# isg-clock-generator-rev1.net
KiCad netlist of a schematic drawn in EAGLE
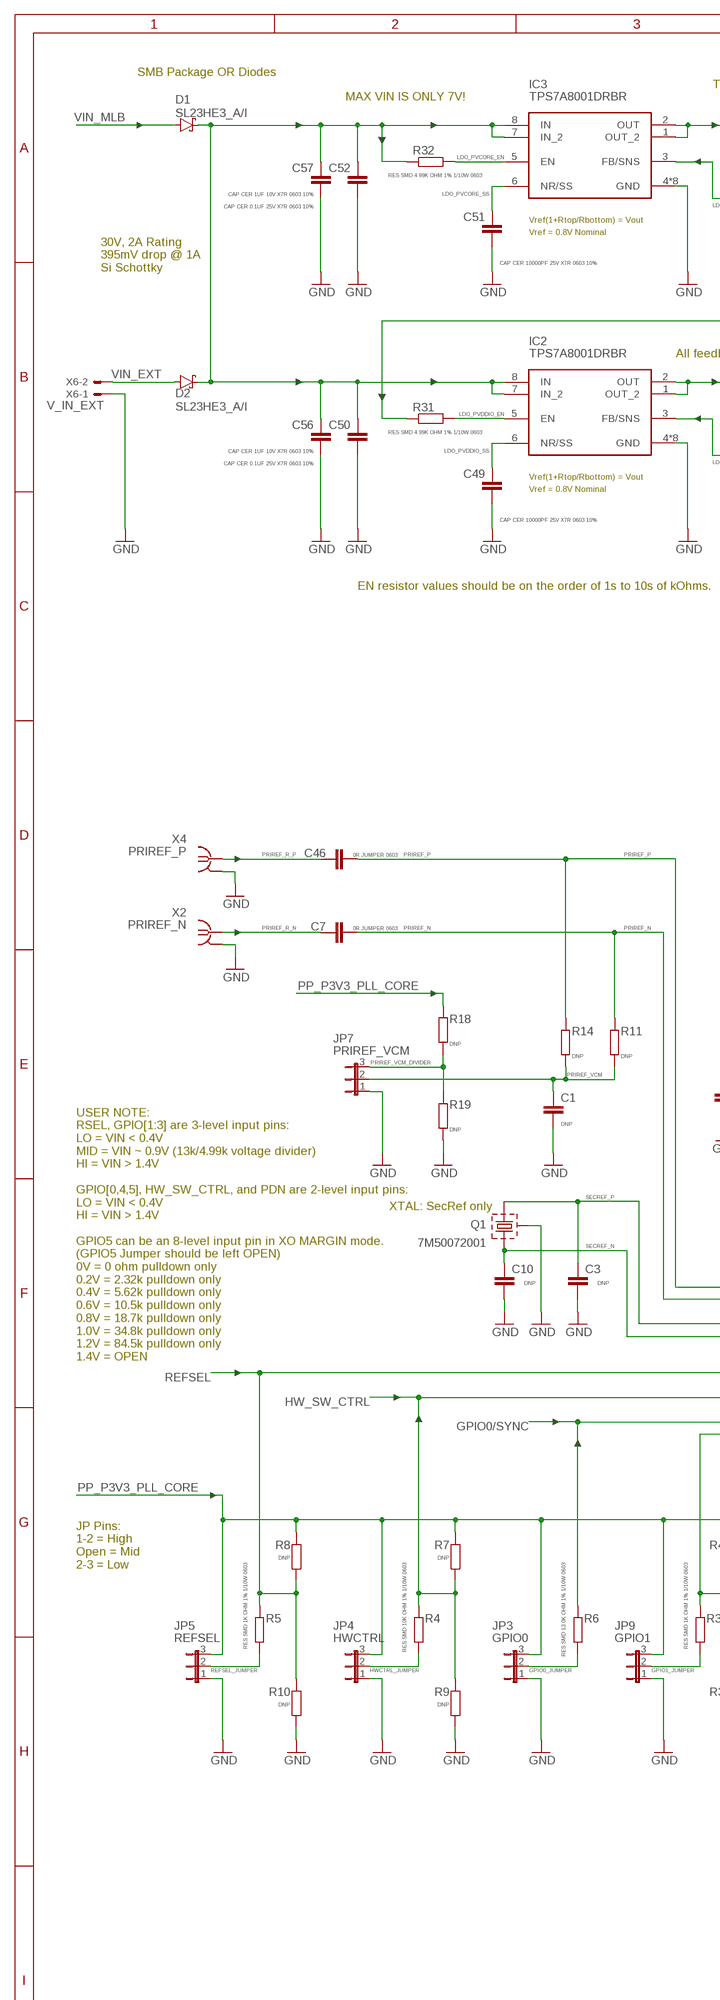
[diagram p0: schematic, sheet 1, part 1 of 2]
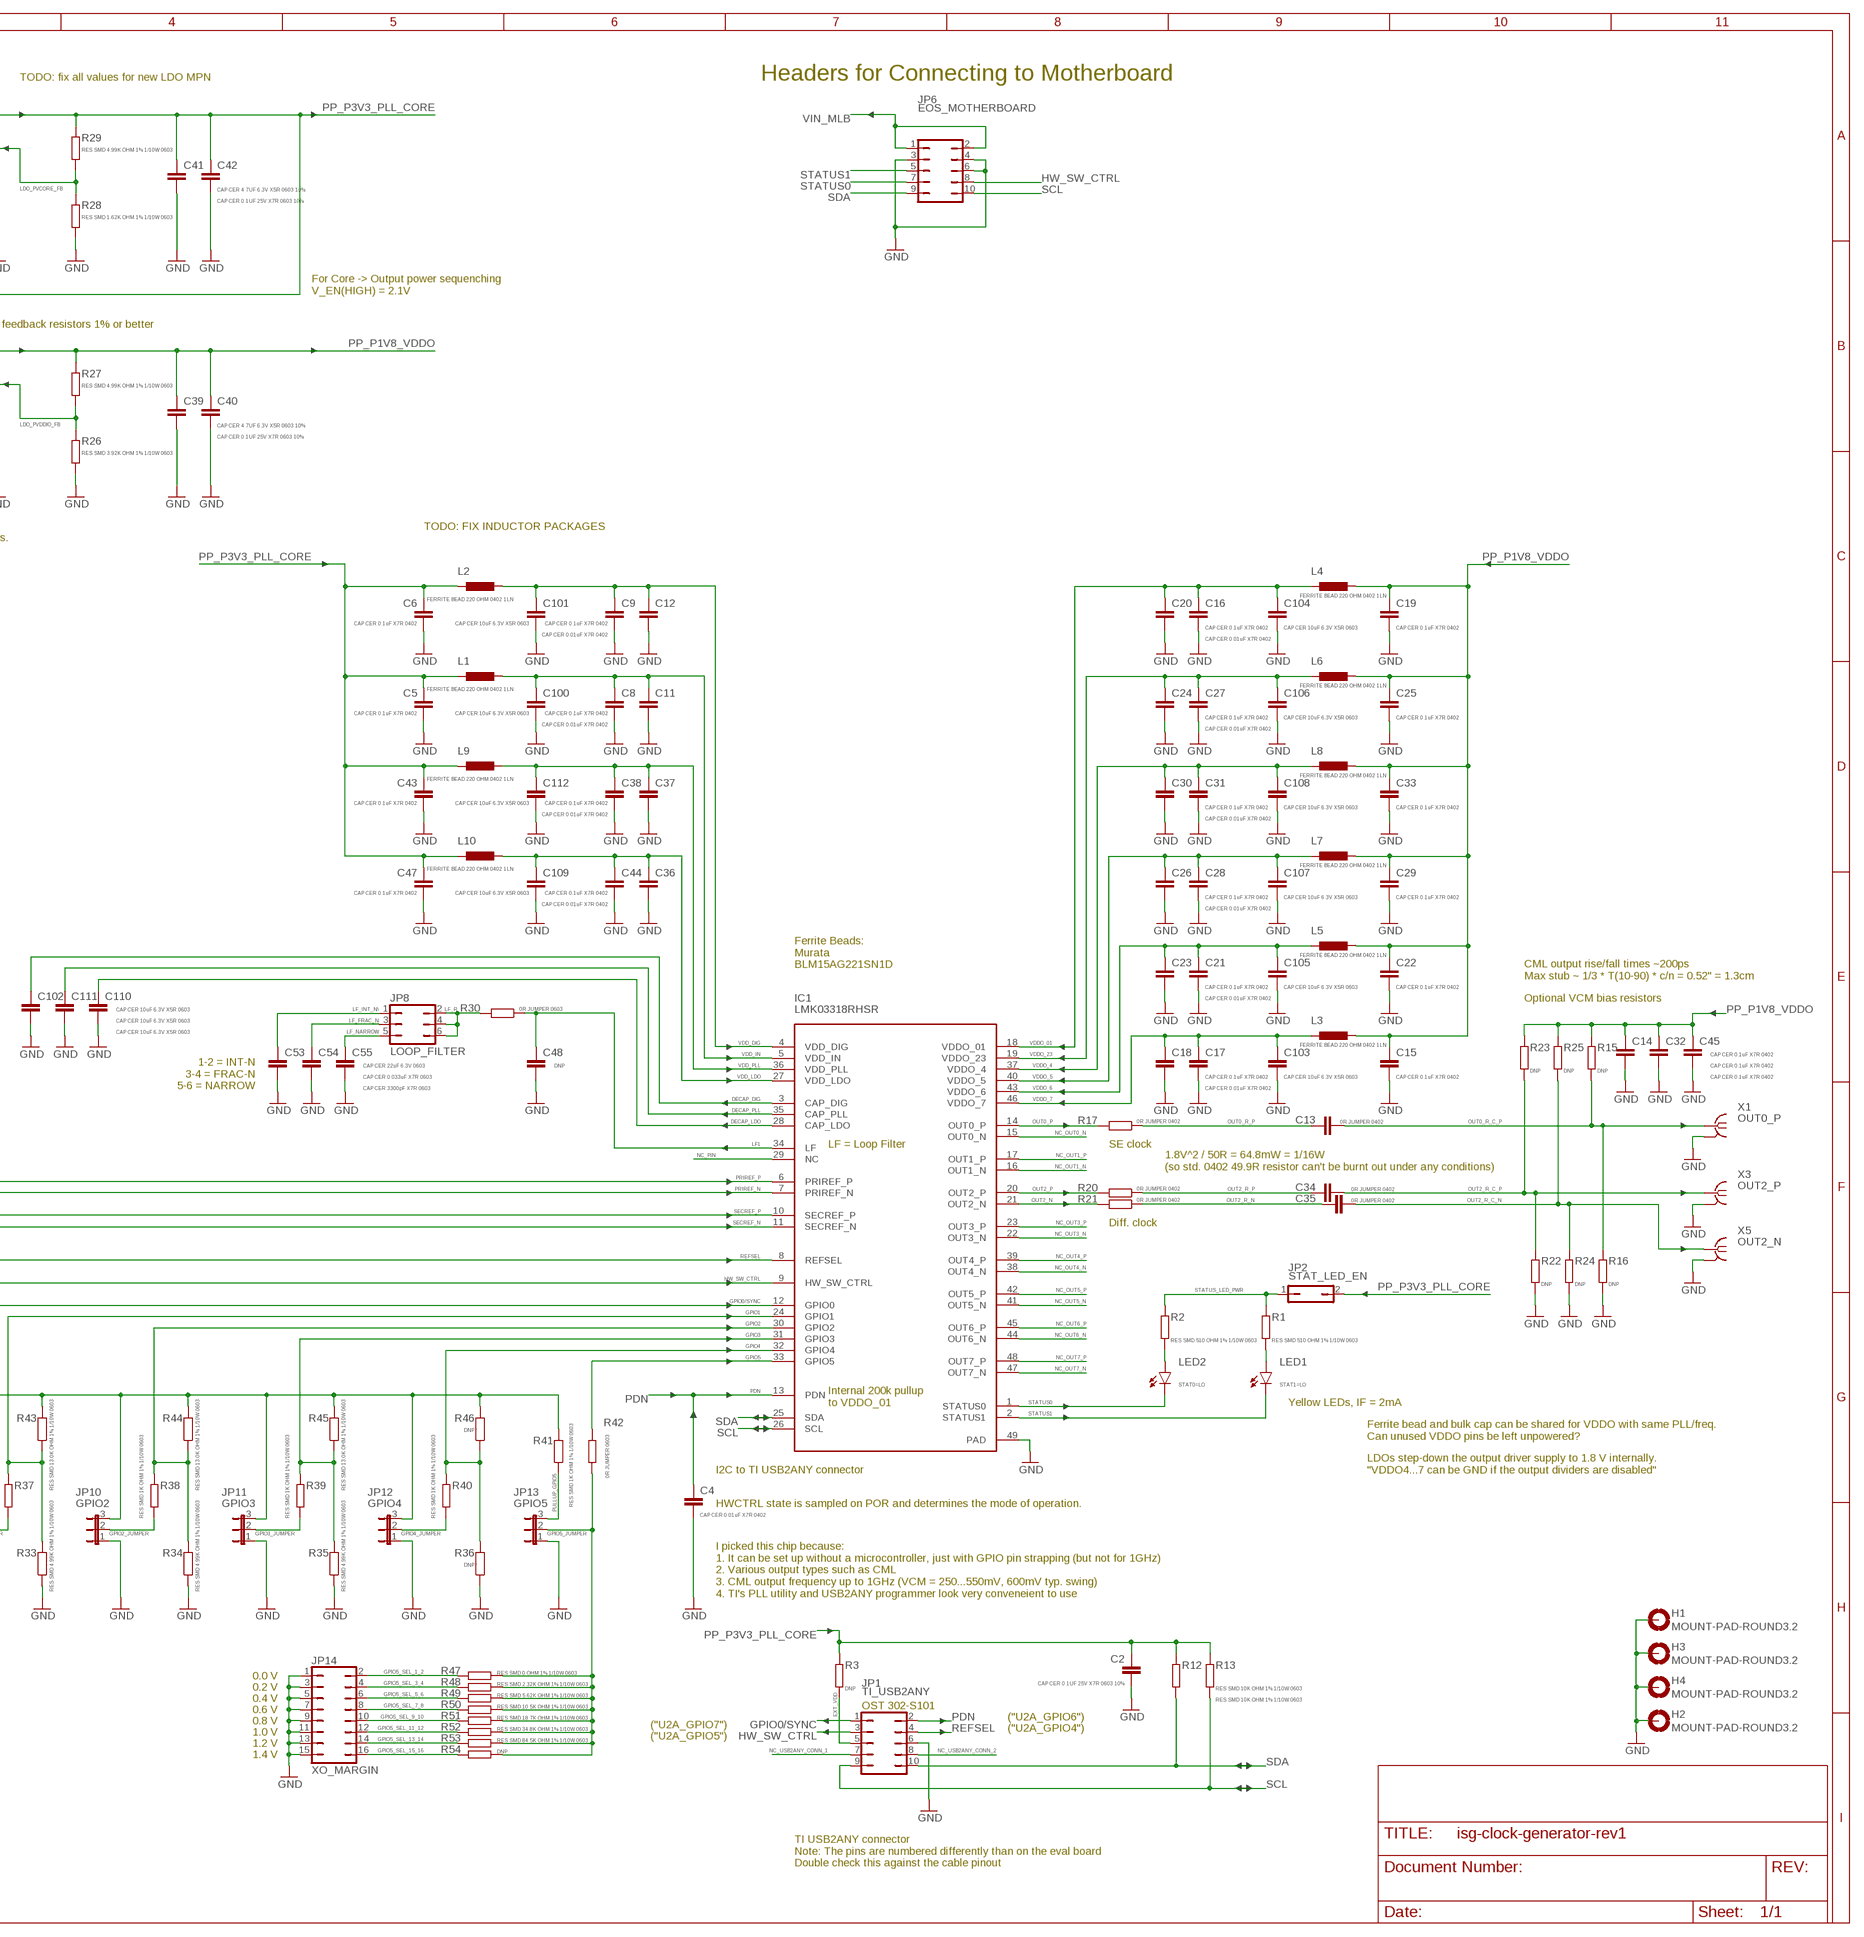
[diagram p1: schematic, sheet 1, part 2 of 2]

(export (version "E")
  (design (tool "Eeschema 10.0.6"))
  (components
    (comp (ref "C1")
      (value "DNP")
      (footprint "eagle-import:C0603")
      (libsource (lib "eagle-import") (part "C-EUC0603"))
    )
    (comp (ref "C2")
      (value "CAP CER 0.1UF 25V X7R 0603 10%")
      (footprint "eagle-import:C0603")
      (libsource (lib "eagle-import") (part "C-EUC0603"))
    )
    (comp (ref "C3")
      (value "DNP")
      (footprint "eagle-import:C0603")
      (libsource (lib "eagle-import") (part "C-EUC0603"))
    )
    (comp (ref "C4")
      (value "CAP CER 0.01uF X7R 0402")
      (footprint "eagle-import:C0402")
      (libsource (lib "eagle-import") (part "C-EUC0402"))
    )
    (comp (ref "C5")
      (value "CAP CER 0.1uF X7R 0402")
      (footprint "eagle-import:C0402")
      (libsource (lib "eagle-import") (part "C-EUC0402"))
    )
    (comp (ref "C6")
      (value "CAP CER 0.1uF X7R 0402")
      (footprint "eagle-import:C0402")
      (libsource (lib "eagle-import") (part "C-EUC0402"))
    )
    (comp (ref "C7")
      (value "0R JUMPER 0603")
      (footprint "eagle-import:C0603")
      (libsource (lib "eagle-import") (part "C-EUC0603"))
    )
    (comp (ref "C8")
      (value "CAP CER 0.1uF X7R 0402")
      (footprint "eagle-import:C0402")
      (libsource (lib "eagle-import") (part "C-EUC0402"))
    )
    (comp (ref "C9")
      (value "CAP CER 0.1uF X7R 0402")
      (footprint "eagle-import:C0402")
      (libsource (lib "eagle-import") (part "C-EUC0402"))
    )
    (comp (ref "C10")
      (value "DNP")
      (footprint "eagle-import:C0603")
      (libsource (lib "eagle-import") (part "C-EUC0603"))
    )
    (comp (ref "C11")
      (value "CAP CER 0.01uF X7R 0402")
      (footprint "eagle-import:C0402")
      (libsource (lib "eagle-import") (part "C-EUC0402"))
    )
    (comp (ref "C12")
      (value "CAP CER 0.01uF X7R 0402")
      (footprint "eagle-import:C0402")
      (libsource (lib "eagle-import") (part "C-EUC0402"))
    )
    (comp (ref "C13")
      (value "0R JUMPER 0402")
      (footprint "eagle-import:C0402")
      (libsource (lib "eagle-import") (part "C-EUC0402"))
    )
    (comp (ref "C14")
      (value "CAP CER 0.1uF X7R 0402")
      (footprint "eagle-import:C0402")
      (libsource (lib "eagle-import") (part "C-EUC0402"))
    )
    (comp (ref "C15")
      (value "CAP CER 0.1uF X7R 0402")
      (footprint "eagle-import:C0402")
      (libsource (lib "eagle-import") (part "C-EUC0402"))
    )
    (comp (ref "C16")
      (value "CAP CER 0.1uF X7R 0402")
      (footprint "eagle-import:C0402")
      (libsource (lib "eagle-import") (part "C-EUC0402"))
    )
    (comp (ref "C17")
      (value "CAP CER 0.1uF X7R 0402")
      (footprint "eagle-import:C0402")
      (libsource (lib "eagle-import") (part "C-EUC0402"))
    )
    (comp (ref "C18")
      (value "CAP CER 0.01uF X7R 0402")
      (footprint "eagle-import:C0402")
      (libsource (lib "eagle-import") (part "C-EUC0402"))
    )
    (comp (ref "C19")
      (value "CAP CER 0.1uF X7R 0402")
      (footprint "eagle-import:C0402")
      (libsource (lib "eagle-import") (part "C-EUC0402"))
    )
    (comp (ref "C20")
      (value "CAP CER 0.01uF X7R 0402")
      (footprint "eagle-import:C0402")
      (libsource (lib "eagle-import") (part "C-EUC0402"))
    )
    (comp (ref "C21")
      (value "CAP CER 0.1uF X7R 0402")
      (footprint "eagle-import:C0402")
      (libsource (lib "eagle-import") (part "C-EUC0402"))
    )
    (comp (ref "C22")
      (value "CAP CER 0.1uF X7R 0402")
      (footprint "eagle-import:C0402")
      (libsource (lib "eagle-import") (part "C-EUC0402"))
    )
    (comp (ref "C23")
      (value "CAP CER 0.01uF X7R 0402")
      (footprint "eagle-import:C0402")
      (libsource (lib "eagle-import") (part "C-EUC0402"))
    )
    (comp (ref "C24")
      (value "CAP CER 0.01uF X7R 0402")
      (footprint "eagle-import:C0402")
      (libsource (lib "eagle-import") (part "C-EUC0402"))
    )
    (comp (ref "C25")
      (value "CAP CER 0.1uF X7R 0402")
      (footprint "eagle-import:C0402")
      (libsource (lib "eagle-import") (part "C-EUC0402"))
    )
    (comp (ref "C26")
      (value "CAP CER 0.01uF X7R 0402")
      (footprint "eagle-import:C0402")
      (libsource (lib "eagle-import") (part "C-EUC0402"))
    )
    (comp (ref "C27")
      (value "CAP CER 0.1uF X7R 0402")
      (footprint "eagle-import:C0402")
      (libsource (lib "eagle-import") (part "C-EUC0402"))
    )
    (comp (ref "C28")
      (value "CAP CER 0.1uF X7R 0402")
      (footprint "eagle-import:C0402")
      (libsource (lib "eagle-import") (part "C-EUC0402"))
    )
    (comp (ref "C29")
      (value "CAP CER 0.1uF X7R 0402")
      (footprint "eagle-import:C0402")
      (libsource (lib "eagle-import") (part "C-EUC0402"))
    )
    (comp (ref "C30")
      (value "CAP CER 0.01uF X7R 0402")
      (footprint "eagle-import:C0402")
      (libsource (lib "eagle-import") (part "C-EUC0402"))
    )
    (comp (ref "C31")
      (value "CAP CER 0.1uF X7R 0402")
      (footprint "eagle-import:C0402")
      (libsource (lib "eagle-import") (part "C-EUC0402"))
    )
    (comp (ref "C32")
      (value "CAP CER 0.1uF X7R 0402")
      (footprint "eagle-import:C0402")
      (libsource (lib "eagle-import") (part "C-EUC0402"))
    )
    (comp (ref "C33")
      (value "CAP CER 0.1uF X7R 0402")
      (footprint "eagle-import:C0402")
      (libsource (lib "eagle-import") (part "C-EUC0402"))
    )
    (comp (ref "C34")
      (value "0R JUMPER 0402")
      (footprint "eagle-import:C0402")
      (libsource (lib "eagle-import") (part "C-EUC0402"))
    )
    (comp (ref "C35")
      (value "0R JUMPER 0402")
      (footprint "eagle-import:C0402")
      (libsource (lib "eagle-import") (part "C-EUC0402"))
    )
    (comp (ref "C36")
      (value "CAP CER 0.01uF X7R 0402")
      (footprint "eagle-import:C0402")
      (libsource (lib "eagle-import") (part "C-EUC0402"))
    )
    (comp (ref "C37")
      (value "CAP CER 0.01uF X7R 0402")
      (footprint "eagle-import:C0402")
      (libsource (lib "eagle-import") (part "C-EUC0402"))
    )
    (comp (ref "C38")
      (value "CAP CER 0.1uF X7R 0402")
      (footprint "eagle-import:C0402")
      (libsource (lib "eagle-import") (part "C-EUC0402"))
    )
    (comp (ref "C39")
      (value "CAP CER 0.1UF 25V X7R 0603 10%")
      (footprint "eagle-import:C0603")
      (libsource (lib "eagle-import") (part "C-EUC0603"))
    )
    (comp (ref "C40")
      (value "CAP CER 4.7UF 6.3V X5R 0603 10%")
      (footprint "eagle-import:C0603")
      (libsource (lib "eagle-import") (part "C-EUC0603"))
    )
    (comp (ref "C41")
      (value "CAP CER 0.1UF 25V X7R 0603 10%")
      (footprint "eagle-import:C0603")
      (libsource (lib "eagle-import") (part "C-EUC0603"))
    )
    (comp (ref "C42")
      (value "CAP CER 4.7UF 6.3V X5R 0603 10%")
      (footprint "eagle-import:C0603")
      (libsource (lib "eagle-import") (part "C-EUC0603"))
    )
    (comp (ref "C43")
      (value "CAP CER 0.1uF X7R 0402")
      (footprint "eagle-import:C0402")
      (libsource (lib "eagle-import") (part "C-EUC0402"))
    )
    (comp (ref "C44")
      (value "CAP CER 0.1uF X7R 0402")
      (footprint "eagle-import:C0402")
      (libsource (lib "eagle-import") (part "C-EUC0402"))
    )
    (comp (ref "C45")
      (value "CAP CER 0.1uF X7R 0402")
      (footprint "eagle-import:C0402")
      (libsource (lib "eagle-import") (part "C-EUC0402"))
    )
    (comp (ref "C46")
      (value "0R JUMPER 0603")
      (footprint "eagle-import:C0603")
      (libsource (lib "eagle-import") (part "C-EUC0603"))
    )
    (comp (ref "C47")
      (value "CAP CER 0.1uF X7R 0402")
      (footprint "eagle-import:C0402")
      (libsource (lib "eagle-import") (part "C-EUC0402"))
    )
    (comp (ref "C48")
      (value "DNP")
      (footprint "eagle-import:C0603")
      (libsource (lib "eagle-import") (part "C-EUC0603"))
    )
    (comp (ref "C49")
      (value "CAP CER 10000PF 25V X7R 0603 10%")
      (footprint "eagle-import:C0603")
      (libsource (lib "eagle-import") (part "C-EUC0603"))
    )
    (comp (ref "C50")
      (value "CAP CER 0.1UF 25V X7R 0603 10%")
      (footprint "eagle-import:C0603")
      (libsource (lib "eagle-import") (part "C-EUC0603"))
    )
    (comp (ref "C51")
      (value "CAP CER 10000PF 25V X7R 0603 10%")
      (footprint "eagle-import:C0603")
      (libsource (lib "eagle-import") (part "C-EUC0603"))
    )
    (comp (ref "C52")
      (value "CAP CER 0.1UF 25V X7R 0603 10%")
      (footprint "eagle-import:C0603")
      (libsource (lib "eagle-import") (part "C-EUC0603"))
    )
    (comp (ref "C53")
      (value "CAP CER 3300pF X7R 0603")
      (footprint "eagle-import:C0603")
      (libsource (lib "eagle-import") (part "C-EUC0603"))
    )
    (comp (ref "C54")
      (value "CAP CER 0.033uF X7R 0603")
      (footprint "eagle-import:C0603")
      (libsource (lib "eagle-import") (part "C-EUC0603"))
    )
    (comp (ref "C55")
      (value "CAP CER 22uF 6.3V 0603")
      (footprint "eagle-import:C0603")
      (libsource (lib "eagle-import") (part "C-EUC0603"))
    )
    (comp (ref "C56")
      (value "CAP CER 1UF 10V X7R 0603 10%")
      (footprint "eagle-import:C0603")
      (libsource (lib "eagle-import") (part "C-EUC0603"))
    )
    (comp (ref "C57")
      (value "CAP CER 1UF 10V X7R 0603 10%")
      (footprint "eagle-import:C0603")
      (libsource (lib "eagle-import") (part "C-EUC0603"))
    )
    (comp (ref "C100")
      (value "CAP CER 10uF 6.3V X5R 0603")
      (footprint "eagle-import:C0603")
      (libsource (lib "eagle-import") (part "C-EUC0603"))
    )
    (comp (ref "C101")
      (value "CAP CER 10uF 6.3V X5R 0603")
      (footprint "eagle-import:C0603")
      (libsource (lib "eagle-import") (part "C-EUC0603"))
    )
    (comp (ref "C102")
      (value "CAP CER 10uF 6.3V X5R 0603")
      (footprint "eagle-import:C0603")
      (libsource (lib "eagle-import") (part "C-EUC0603"))
    )
    (comp (ref "C103")
      (value "CAP CER 10uF 6.3V X5R 0603")
      (footprint "eagle-import:C0603")
      (libsource (lib "eagle-import") (part "C-EUC0603"))
    )
    (comp (ref "C104")
      (value "CAP CER 10uF 6.3V X5R 0603")
      (footprint "eagle-import:C0603")
      (libsource (lib "eagle-import") (part "C-EUC0603"))
    )
    (comp (ref "C105")
      (value "CAP CER 10uF 6.3V X5R 0603")
      (footprint "eagle-import:C0603")
      (libsource (lib "eagle-import") (part "C-EUC0603"))
    )
    (comp (ref "C106")
      (value "CAP CER 10uF 6.3V X5R 0603")
      (footprint "eagle-import:C0603")
      (libsource (lib "eagle-import") (part "C-EUC0603"))
    )
    (comp (ref "C107")
      (value "CAP CER 10uF 6.3V X5R 0603")
      (footprint "eagle-import:C0603")
      (libsource (lib "eagle-import") (part "C-EUC0603"))
    )
    (comp (ref "C108")
      (value "CAP CER 10uF 6.3V X5R 0603")
      (footprint "eagle-import:C0603")
      (libsource (lib "eagle-import") (part "C-EUC0603"))
    )
    (comp (ref "C109")
      (value "CAP CER 10uF 6.3V X5R 0603")
      (footprint "eagle-import:C0603")
      (libsource (lib "eagle-import") (part "C-EUC0603"))
    )
    (comp (ref "C110")
      (value "CAP CER 10uF 6.3V X5R 0603")
      (footprint "eagle-import:C0603")
      (libsource (lib "eagle-import") (part "C-EUC0603"))
    )
    (comp (ref "C111")
      (value "CAP CER 10uF 6.3V X5R 0603")
      (footprint "eagle-import:C0603")
      (libsource (lib "eagle-import") (part "C-EUC0603"))
    )
    (comp (ref "C112")
      (value "CAP CER 10uF 6.3V X5R 0603")
      (footprint "eagle-import:C0603")
      (libsource (lib "eagle-import") (part "C-EUC0603"))
    )
    (comp (ref "D1")
      (value "SL23HE3_A/I")
      (footprint "eagle-import:SMB")
      (libsource (lib "eagle-import") (part "SCHOTTKY-DIODESMD"))
    )
    (comp (ref "D2")
      (value "SL23HE3_A/I")
      (footprint "eagle-import:SMB")
      (libsource (lib "eagle-import") (part "SCHOTTKY-DIODESMD"))
    )
    (comp (ref "H1")
      (value "MOUNT-PAD-ROUND3.2")
      (footprint "eagle-import:3,2-PAD")
      (libsource (lib "eagle-import") (part "MOUNT-PAD-ROUND3.2"))
    )
    (comp (ref "H2")
      (value "MOUNT-PAD-ROUND3.2")
      (footprint "eagle-import:3,2-PAD")
      (libsource (lib "eagle-import") (part "MOUNT-PAD-ROUND3.2"))
    )
    (comp (ref "H3")
      (value "MOUNT-PAD-ROUND3.2")
      (footprint "eagle-import:3,2-PAD")
      (libsource (lib "eagle-import") (part "MOUNT-PAD-ROUND3.2"))
    )
    (comp (ref "H4")
      (value "MOUNT-PAD-ROUND3.2")
      (footprint "eagle-import:3,2-PAD")
      (libsource (lib "eagle-import") (part "MOUNT-PAD-ROUND3.2"))
    )
    (comp (ref "IC1")
      (value "LMK03318RHSR")
      (footprint "eagle-import:RHS0048A_NV")
      (libsource (lib "eagle-import") (part "LMK03318RHSRRHS0048A_NV"))
    )
    (comp (ref "IC2")
      (value "TPS7A8001DRBR")
      (footprint "eagle-import:DRB8_1P75X1P5")
      (libsource (lib "eagle-import") (part "TPS7A8001DRBR"))
    )
    (comp (ref "IC3")
      (value "TPS7A8001DRBR")
      (footprint "eagle-import:DRB8_1P75X1P5")
      (libsource (lib "eagle-import") (part "TPS7A8001DRBR"))
    )
    (comp (ref "JP1")
      (value "TI_USB2ANY")
      (footprint "eagle-import:CON_OST_302-S101")
      (libsource (lib "eagle-import") (part "CON_OST_302-S101"))
    )
    (comp (ref "JP2")
      (value "STAT_LED_EN")
      (footprint "eagle-import:JP1")
      (libsource (lib "eagle-import") (part "JP1Q"))
    )
    (comp (ref "JP3")
      (value "GPIO0")
      (footprint "eagle-import:JP2_ROUND")
      (libsource (lib "eagle-import") (part "JP2E"))
    )
    (comp (ref "JP4")
      (value "HWCTRL")
      (footprint "eagle-import:JP2_ROUND")
      (libsource (lib "eagle-import") (part "JP2E"))
    )
    (comp (ref "JP5")
      (value "REFSEL")
      (footprint "eagle-import:JP2_ROUND")
      (libsource (lib "eagle-import") (part "JP2E"))
    )
    (comp (ref "JP6")
      (value "EOS_MOTHERBOARD")
      (footprint "eagle-import:JP5Q")
      (libsource (lib "eagle-import") (part "JP5Q"))
    )
    (comp (ref "JP7")
      (value "PRIREF_VCM")
      (footprint "eagle-import:JP2_ROUND")
      (libsource (lib "eagle-import") (part "JP2E"))
    )
    (comp (ref "JP8")
      (value "LOOP_FILTER")
      (footprint "eagle-import:JP3Q")
      (libsource (lib "eagle-import") (part "JP3Q"))
    )
    (comp (ref "JP9")
      (value "GPIO1")
      (footprint "eagle-import:JP2_ROUND")
      (libsource (lib "eagle-import") (part "JP2E"))
    )
    (comp (ref "JP10")
      (value "GPIO2")
      (footprint "eagle-import:JP2_ROUND")
      (libsource (lib "eagle-import") (part "JP2E"))
    )
    (comp (ref "JP11")
      (value "GPIO3")
      (footprint "eagle-import:JP2_ROUND")
      (libsource (lib "eagle-import") (part "JP2E"))
    )
    (comp (ref "JP12")
      (value "GPIO4")
      (footprint "eagle-import:JP2_ROUND")
      (libsource (lib "eagle-import") (part "JP2E"))
    )
    (comp (ref "JP13")
      (value "GPIO5")
      (footprint "eagle-import:JP2_ROUND")
      (libsource (lib "eagle-import") (part "JP2E"))
    )
    (comp (ref "JP14")
      (value "XO_MARGIN")
      (footprint "eagle-import:JP8Q")
      (libsource (lib "eagle-import") (part "JP8Q"))
    )
    (comp (ref "L1")
      (value "FERRITE BEAD 220 OHM 0402 1LN")
      (footprint "eagle-import:R0402")
      (libsource (lib "eagle-import") (part "INDUCTOR0402"))
    )
    (comp (ref "L2")
      (value "FERRITE BEAD 220 OHM 0402 1LN")
      (footprint "eagle-import:R0402")
      (libsource (lib "eagle-import") (part "INDUCTOR0402"))
    )
    (comp (ref "L3")
      (value "FERRITE BEAD 220 OHM 0402 1LN")
      (footprint "eagle-import:R0402")
      (libsource (lib "eagle-import") (part "INDUCTOR0402"))
    )
    (comp (ref "L4")
      (value "FERRITE BEAD 220 OHM 0402 1LN")
      (footprint "eagle-import:R0402")
      (libsource (lib "eagle-import") (part "INDUCTOR0402"))
    )
    (comp (ref "L5")
      (value "FERRITE BEAD 220 OHM 0402 1LN")
      (footprint "eagle-import:R0402")
      (libsource (lib "eagle-import") (part "INDUCTOR0402"))
    )
    (comp (ref "L6")
      (value "FERRITE BEAD 220 OHM 0402 1LN")
      (footprint "eagle-import:R0402")
      (libsource (lib "eagle-import") (part "INDUCTOR0402"))
    )
    (comp (ref "L7")
      (value "FERRITE BEAD 220 OHM 0402 1LN")
      (footprint "eagle-import:R0402")
      (libsource (lib "eagle-import") (part "INDUCTOR0402"))
    )
    (comp (ref "L8")
      (value "FERRITE BEAD 220 OHM 0402 1LN")
      (footprint "eagle-import:R0402")
      (libsource (lib "eagle-import") (part "INDUCTOR0402"))
    )
    (comp (ref "L9")
      (value "FERRITE BEAD 220 OHM 0402 1LN")
      (footprint "eagle-import:R0402")
      (libsource (lib "eagle-import") (part "INDUCTOR0402"))
    )
    (comp (ref "L10")
      (value "FERRITE BEAD 220 OHM 0402 1LN")
      (footprint "eagle-import:R0402")
      (libsource (lib "eagle-import") (part "INDUCTOR0402"))
    )
    (comp (ref "LED1")
      (value "STAT1=LO")
      (footprint "eagle-import:CHIP-LED0805")
      (libsource (lib "eagle-import") (part "LEDCHIP-LED0805"))
    )
    (comp (ref "LED2")
      (value "STAT0=LO")
      (footprint "eagle-import:CHIP-LED0805")
      (libsource (lib "eagle-import") (part "LEDCHIP-LED0805"))
    )
    (comp (ref "Q1")
      (value "7M50072001")
      (footprint "eagle-import:3.2X2.5_KX-7")
      (libsource (lib "eagle-import") (part "KX-7"))
    )
    (comp (ref "R1")
      (value "RES SMD 510 OHM 1% 1/10W 0603")
      (footprint "eagle-import:R0603")
      (libsource (lib "eagle-import") (part "R-EU_R0603"))
    )
    (comp (ref "R2")
      (value "RES SMD 510 OHM 1% 1/10W 0603")
      (footprint "eagle-import:R0603")
      (libsource (lib "eagle-import") (part "R-EU_R0603"))
    )
    (comp (ref "R3")
      (value "DNP")
      (footprint "eagle-import:R0603")
      (libsource (lib "eagle-import") (part "R-EU_R0603"))
    )
    (comp (ref "R4")
      (value "RES SMD 10K OHM 1% 1/10W 0603")
      (footprint "eagle-import:R0603")
      (libsource (lib "eagle-import") (part "R-EU_R0603"))
    )
    (comp (ref "R5")
      (value "RES SMD 1K OHM 1% 1/10W 0603")
      (footprint "eagle-import:R0603")
      (libsource (lib "eagle-import") (part "R-EU_R0603"))
    )
    (comp (ref "R6")
      (value "RES SMD 13.0K OHM 1% 1/10W 0603")
      (footprint "eagle-import:R0603")
      (libsource (lib "eagle-import") (part "R-EU_R0603"))
    )
    (comp (ref "R7")
      (value "DNP")
      (footprint "eagle-import:R0603")
      (libsource (lib "eagle-import") (part "R-EU_R0603"))
    )
    (comp (ref "R8")
      (value "DNP")
      (footprint "eagle-import:R0603")
      (libsource (lib "eagle-import") (part "R-EU_R0603"))
    )
    (comp (ref "R9")
      (value "DNP")
      (footprint "eagle-import:R0603")
      (libsource (lib "eagle-import") (part "R-EU_R0603"))
    )
    (comp (ref "R10")
      (value "DNP")
      (footprint "eagle-import:R0603")
      (libsource (lib "eagle-import") (part "R-EU_R0603"))
    )
    (comp (ref "R11")
      (value "DNP")
      (footprint "eagle-import:R0603")
      (libsource (lib "eagle-import") (part "R-EU_R0603"))
    )
    (comp (ref "R12")
      (value "RES SMD 10K OHM 1% 1/10W 0603")
      (footprint "eagle-import:R0603")
      (libsource (lib "eagle-import") (part "R-EU_R0603"))
    )
    (comp (ref "R13")
      (value "RES SMD 10K OHM 1% 1/10W 0603")
      (footprint "eagle-import:R0603")
      (libsource (lib "eagle-import") (part "R-EU_R0603"))
    )
    (comp (ref "R14")
      (value "DNP")
      (footprint "eagle-import:R0603")
      (libsource (lib "eagle-import") (part "R-EU_R0603"))
    )
    (comp (ref "R15")
      (value "DNP")
      (footprint "eagle-import:R0402")
      (libsource (lib "eagle-import") (part "R-EU_R0402"))
    )
    (comp (ref "R16")
      (value "DNP")
      (footprint "eagle-import:R0402")
      (libsource (lib "eagle-import") (part "R-EU_R0402"))
    )
    (comp (ref "R17")
      (value "0R JUMPER 0402")
      (footprint "eagle-import:R0402")
      (libsource (lib "eagle-import") (part "R-EU_R0402"))
    )
    (comp (ref "R18")
      (value "DNP")
      (footprint "eagle-import:R0603")
      (libsource (lib "eagle-import") (part "R-EU_R0603"))
    )
    (comp (ref "R19")
      (value "DNP")
      (footprint "eagle-import:R0603")
      (libsource (lib "eagle-import") (part "R-EU_R0603"))
    )
    (comp (ref "R20")
      (value "0R JUMPER 0402")
      (footprint "eagle-import:R0402")
      (libsource (lib "eagle-import") (part "R-EU_R0402"))
    )
    (comp (ref "R21")
      (value "0R JUMPER 0402")
      (footprint "eagle-import:R0402")
      (libsource (lib "eagle-import") (part "R-EU_R0402"))
    )
    (comp (ref "R22")
      (value "DNP")
      (footprint "eagle-import:R0402")
      (libsource (lib "eagle-import") (part "R-EU_R0402"))
    )
    (comp (ref "R23")
      (value "DNP")
      (footprint "eagle-import:R0402")
      (libsource (lib "eagle-import") (part "R-EU_R0402"))
    )
    (comp (ref "R24")
      (value "DNP")
      (footprint "eagle-import:R0402")
      (libsource (lib "eagle-import") (part "R-EU_R0402"))
    )
    (comp (ref "R25")
      (value "DNP")
      (footprint "eagle-import:R0402")
      (libsource (lib "eagle-import") (part "R-EU_R0402"))
    )
    (comp (ref "R26")
      (value "RES SMD 3.92K OHM 1% 1/10W 0603")
      (footprint "eagle-import:R0603")
      (libsource (lib "eagle-import") (part "R-EU_R0603"))
    )
    (comp (ref "R27")
      (value "RES SMD 4.99K OHM 1% 1/10W 0603")
      (footprint "eagle-import:R0603")
      (libsource (lib "eagle-import") (part "R-EU_R0603"))
    )
    (comp (ref "R28")
      (value "RES SMD 1.62K OHM 1% 1/10W 0603")
      (footprint "eagle-import:R0603")
      (libsource (lib "eagle-import") (part "R-EU_R0603"))
    )
    (comp (ref "R29")
      (value "RES SMD 4.99K OHM 1% 1/10W 0603")
      (footprint "eagle-import:R0603")
      (libsource (lib "eagle-import") (part "R-EU_R0603"))
    )
    (comp (ref "R30")
      (value "0R JUMPER 0603")
      (footprint "eagle-import:R0603")
      (libsource (lib "eagle-import") (part "R-EU_R0603"))
    )
    (comp (ref "R31")
      (value "RES SMD 4.99K OHM 1% 1/10W 0603")
      (footprint "eagle-import:R0603")
      (libsource (lib "eagle-import") (part "R-EU_R0603"))
    )
    (comp (ref "R32")
      (value "RES SMD 4.99K OHM 1% 1/10W 0603")
      (footprint "eagle-import:R0603")
      (libsource (lib "eagle-import") (part "R-EU_R0603"))
    )
    (comp (ref "R33")
      (value "RES SMD 4.99K OHM 1% 1/10W 0603")
      (footprint "eagle-import:R0603")
      (libsource (lib "eagle-import") (part "R-EU_R0603"))
    )
    (comp (ref "R34")
      (value "RES SMD 4.99K OHM 1% 1/10W 0603")
      (footprint "eagle-import:R0603")
      (libsource (lib "eagle-import") (part "R-EU_R0603"))
    )
    (comp (ref "R35")
      (value "RES SMD 4.99K OHM 1% 1/10W 0603")
      (footprint "eagle-import:R0603")
      (libsource (lib "eagle-import") (part "R-EU_R0603"))
    )
    (comp (ref "R36")
      (value "DNP")
      (footprint "eagle-import:R0603")
      (libsource (lib "eagle-import") (part "R-EU_R0603"))
    )
    (comp (ref "R37")
      (value "RES SMD 1K OHM 1% 1/10W 0603")
      (footprint "eagle-import:R0603")
      (libsource (lib "eagle-import") (part "R-EU_R0603"))
    )
    (comp (ref "R38")
      (value "RES SMD 1K OHM 1% 1/10W 0603")
      (footprint "eagle-import:R0603")
      (libsource (lib "eagle-import") (part "R-EU_R0603"))
    )
    (comp (ref "R39")
      (value "RES SMD 1K OHM 1% 1/10W 0603")
      (footprint "eagle-import:R0603")
      (libsource (lib "eagle-import") (part "R-EU_R0603"))
    )
    (comp (ref "R40")
      (value "RES SMD 1K OHM 1% 1/10W 0603")
      (footprint "eagle-import:R0603")
      (libsource (lib "eagle-import") (part "R-EU_R0603"))
    )
    (comp (ref "R41")
      (value "RES SMD 1K OHM 1% 1/10W 0603")
      (footprint "eagle-import:R0603")
      (libsource (lib "eagle-import") (part "R-EU_R0603"))
    )
    (comp (ref "R42")
      (value "0R JUMPER 0603")
      (footprint "eagle-import:R0603")
      (libsource (lib "eagle-import") (part "R-EU_R0603"))
    )
    (comp (ref "R43")
      (value "RES SMD 13.0K OHM 1% 1/10W 0603")
      (footprint "eagle-import:R0603")
      (libsource (lib "eagle-import") (part "R-EU_R0603"))
    )
    (comp (ref "R44")
      (value "RES SMD 13.0K OHM 1% 1/10W 0603")
      (footprint "eagle-import:R0603")
      (libsource (lib "eagle-import") (part "R-EU_R0603"))
    )
    (comp (ref "R45")
      (value "RES SMD 13.0K OHM 1% 1/10W 0603")
      (footprint "eagle-import:R0603")
      (libsource (lib "eagle-import") (part "R-EU_R0603"))
    )
    (comp (ref "R46")
      (value "DNP")
      (footprint "eagle-import:R0603")
      (libsource (lib "eagle-import") (part "R-EU_R0603"))
    )
    (comp (ref "R47")
      (value "RES SMD 0 OHM 1% 1/10W 0603")
      (footprint "eagle-import:R0603")
      (libsource (lib "eagle-import") (part "R-EU_R0603"))
    )
    (comp (ref "R48")
      (value "RES SMD 2.32K OHM 1% 1/10W 0603")
      (footprint "eagle-import:R0603")
      (libsource (lib "eagle-import") (part "R-EU_R0603"))
    )
    (comp (ref "R49")
      (value "RES SMD 5.62K OHM 1% 1/10W 0603")
      (footprint "eagle-import:R0603")
      (libsource (lib "eagle-import") (part "R-EU_R0603"))
    )
    (comp (ref "R50")
      (value "RES SMD 10.5K OHM 1% 1/10W 0603")
      (footprint "eagle-import:R0603")
      (libsource (lib "eagle-import") (part "R-EU_R0603"))
    )
    (comp (ref "R51")
      (value "RES SMD 18.7K OHM 1% 1/10W 0603")
      (footprint "eagle-import:R0603")
      (libsource (lib "eagle-import") (part "R-EU_R0603"))
    )
    (comp (ref "R52")
      (value "RES SMD 34.8K OHM 1% 1/10W 0603")
      (footprint "eagle-import:R0603")
      (libsource (lib "eagle-import") (part "R-EU_R0603"))
    )
    (comp (ref "R53")
      (value "RES SMD 84.5K OHM 1% 1/10W 0603")
      (footprint "eagle-import:R0603")
      (libsource (lib "eagle-import") (part "R-EU_R0603"))
    )
    (comp (ref "R54")
      (value "DNP")
      (footprint "eagle-import:R0603")
      (libsource (lib "eagle-import") (part "R-EU_R0603"))
    )
    (comp (ref "X1")
      (value "OUT0_P")
      (footprint "eagle-import:J502-ND-142-0701-881_886")
      (fields (field (name "MF") "JOHNSON COMPONENTS") (field (name "MPN") "142-0701-881"))
      (libsource (lib "eagle-import") (part "SMA-142-0701-881/886"))
    )
    (comp (ref "X2")
      (value "PRIREF_N")
      (footprint "eagle-import:J502-ND-142-0701-881_886")
      (fields (field (name "MF") "JOHNSON COMPONENTS") (field (name "MPN") "142-0701-881"))
      (libsource (lib "eagle-import") (part "SMA-142-0701-881/886"))
    )
    (comp (ref "X3")
      (value "OUT2_P")
      (footprint "eagle-import:J502-ND-142-0701-881_886")
      (fields (field (name "MF") "JOHNSON COMPONENTS") (field (name "MPN") "142-0701-881"))
      (libsource (lib "eagle-import") (part "SMA-142-0701-881/886"))
    )
    (comp (ref "X4")
      (value "PRIREF_P")
      (footprint "eagle-import:J502-ND-142-0701-881_886")
      (fields (field (name "MF") "JOHNSON COMPONENTS") (field (name "MPN") "142-0701-881"))
      (libsource (lib "eagle-import") (part "SMA-142-0701-881/886"))
    )
    (comp (ref "X5")
      (value "OUT2_N")
      (footprint "eagle-import:J502-ND-142-0701-881_886")
      (fields (field (name "MF") "JOHNSON COMPONENTS") (field (name "MPN") "142-0701-881"))
      (libsource (lib "eagle-import") (part "SMA-142-0701-881/886"))
    )
    (comp (ref "X6")
      (value "V_IN_EXT")
      (footprint "eagle-import:22-23-2021")
      (fields (field (name "MF") "MOLEX") (field (name "MPN") "22-23-2021"))
      (libsource (lib "eagle-import") (part "22-23-2021"))
    )
  )
  (nets
    (net (code "1") (name "/DECAP_DIG") (class "Default")
      (node (ref "C102") (pin "1") (pinfunction "1_1") (pintype "passive"))
      (node (ref "IC1") (pin "3") (pinfunction "CAP_DIG_3") (pintype "passive"))
    )
    (net (code "2") (name "/DECAP_LDO") (class "Default")
      (node (ref "C110") (pin "1") (pinfunction "1_1") (pintype "passive"))
      (node (ref "IC1") (pin "28") (pinfunction "CAP_LDO_28") (pintype "passive"))
    )
    (net (code "3") (name "/DECAP_PLL") (class "Default")
      (node (ref "C111") (pin "1") (pinfunction "1_1") (pintype "passive"))
      (node (ref "IC1") (pin "35") (pinfunction "CAP_PLL_35") (pintype "passive"))
    )
    (net (code "4") (name "/EXT_VDD") (class "Default")
      (node (ref "JP1") (pin "5") (pinfunction "5_5") (pintype "passive"))
      (node (ref "R3") (pin "1") (pinfunction "1_1") (pintype "passive"))
    )
    (net (code "5") (name "/GPIO0_JUMPER") (class "Default")
      (node (ref "JP3") (pin "2") (pinfunction "2_2") (pintype "passive"))
      (node (ref "R6") (pin "1") (pinfunction "1_1") (pintype "passive"))
    )
    (net (code "6") (name "/GPIO0{slash}SYNC") (class "Default")
      (node (ref "IC1") (pin "12") (pinfunction "GPIO0_12") (pintype "bidirectional"))
      (node (ref "JP1") (pin "1") (pinfunction "1_1") (pintype "passive"))
      (node (ref "R6") (pin "2") (pinfunction "2_2") (pintype "passive"))
    )
    (net (code "7") (name "/GPIO1") (class "Default")
      (node (ref "IC1") (pin "24") (pinfunction "GPIO1_24") (pintype "bidirectional"))
      (node (ref "R33") (pin "2") (pinfunction "2_2") (pintype "passive"))
      (node (ref "R37") (pin "2") (pinfunction "2_2") (pintype "passive"))
      (node (ref "R43") (pin "1") (pinfunction "1_1") (pintype "passive"))
    )
    (net (code "8") (name "/GPIO1_JUMPER") (class "Default")
      (node (ref "JP9") (pin "2") (pinfunction "2_2") (pintype "passive"))
      (node (ref "R37") (pin "1") (pinfunction "1_1") (pintype "passive"))
    )
    (net (code "9") (name "/GPIO2") (class "Default")
      (node (ref "IC1") (pin "30") (pinfunction "GPIO2_30") (pintype "bidirectional"))
      (node (ref "R34") (pin "2") (pinfunction "2_2") (pintype "passive"))
      (node (ref "R38") (pin "2") (pinfunction "2_2") (pintype "passive"))
      (node (ref "R44") (pin "1") (pinfunction "1_1") (pintype "passive"))
    )
    (net (code "10") (name "/GPIO2_JUMPER") (class "Default")
      (node (ref "JP10") (pin "2") (pinfunction "2_2") (pintype "passive"))
      (node (ref "R38") (pin "1") (pinfunction "1_1") (pintype "passive"))
    )
    (net (code "11") (name "/GPIO3") (class "Default")
      (node (ref "IC1") (pin "31") (pinfunction "GPIO3_31") (pintype "bidirectional"))
      (node (ref "R35") (pin "2") (pinfunction "2_2") (pintype "passive"))
      (node (ref "R39") (pin "2") (pinfunction "2_2") (pintype "passive"))
      (node (ref "R45") (pin "1") (pinfunction "1_1") (pintype "passive"))
    )
    (net (code "12") (name "/GPIO3_JUMPER") (class "Default")
      (node (ref "JP11") (pin "2") (pinfunction "2_2") (pintype "passive"))
      (node (ref "R39") (pin "1") (pinfunction "1_1") (pintype "passive"))
    )
    (net (code "13") (name "/GPIO4") (class "Default")
      (node (ref "IC1") (pin "32") (pinfunction "GPIO4_32") (pintype "bidirectional"))
      (node (ref "R36") (pin "2") (pinfunction "2_2") (pintype "passive"))
      (node (ref "R40") (pin "2") (pinfunction "2_2") (pintype "passive"))
      (node (ref "R46") (pin "1") (pinfunction "1_1") (pintype "passive"))
    )
    (net (code "14") (name "/GPIO4_JUMPER") (class "Default")
      (node (ref "JP12") (pin "2") (pinfunction "2_2") (pintype "passive"))
      (node (ref "R40") (pin "1") (pinfunction "1_1") (pintype "passive"))
    )
    (net (code "15") (name "/GPIO5") (class "Default")
      (node (ref "IC1") (pin "33") (pinfunction "GPIO5_33") (pintype "bidirectional"))
      (node (ref "R42") (pin "1") (pinfunction "1_1") (pintype "passive"))
    )
    (net (code "16") (name "/GPIO5_JUMPER") (class "Default")
      (node (ref "JP13") (pin "2") (pinfunction "2_2") (pintype "passive"))
      (node (ref "R42") (pin "2") (pinfunction "2_2") (pintype "passive"))
      (node (ref "R47") (pin "1") (pinfunction "1_1") (pintype "passive"))
      (node (ref "R48") (pin "1") (pinfunction "1_1") (pintype "passive"))
      (node (ref "R49") (pin "1") (pinfunction "1_1") (pintype "passive"))
      (node (ref "R50") (pin "1") (pinfunction "1_1") (pintype "passive"))
      (node (ref "R51") (pin "1") (pinfunction "1_1") (pintype "passive"))
      (node (ref "R52") (pin "1") (pinfunction "1_1") (pintype "passive"))
      (node (ref "R53") (pin "1") (pinfunction "1_1") (pintype "passive"))
      (node (ref "R54") (pin "1") (pinfunction "1_1") (pintype "passive"))
    )
    (net (code "17") (name "/GPIO5_SEL_1_2") (class "Default")
      (node (ref "JP14") (pin "2") (pinfunction "2_2") (pintype "passive"))
      (node (ref "R47") (pin "2") (pinfunction "2_2") (pintype "passive"))
    )
    (net (code "18") (name "/GPIO5_SEL_3_4") (class "Default")
      (node (ref "JP14") (pin "4") (pinfunction "4_4") (pintype "passive"))
      (node (ref "R48") (pin "2") (pinfunction "2_2") (pintype "passive"))
    )
    (net (code "19") (name "/GPIO5_SEL_5_6") (class "Default")
      (node (ref "JP14") (pin "6") (pinfunction "6_6") (pintype "passive"))
      (node (ref "R49") (pin "2") (pinfunction "2_2") (pintype "passive"))
    )
    (net (code "20") (name "/GPIO5_SEL_7_8") (class "Default")
      (node (ref "JP14") (pin "8") (pinfunction "8_8") (pintype "passive"))
      (node (ref "R50") (pin "2") (pinfunction "2_2") (pintype "passive"))
    )
    (net (code "21") (name "/GPIO5_SEL_9_10") (class "Default")
      (node (ref "JP14") (pin "10") (pinfunction "10_10") (pintype "passive"))
      (node (ref "R51") (pin "2") (pinfunction "2_2") (pintype "passive"))
    )
    (net (code "22") (name "/GPIO5_SEL_11_12") (class "Default")
      (node (ref "JP14") (pin "12") (pinfunction "12_12") (pintype "passive"))
      (node (ref "R52") (pin "2") (pinfunction "2_2") (pintype "passive"))
    )
    (net (code "23") (name "/GPIO5_SEL_13_14") (class "Default")
      (node (ref "JP14") (pin "14") (pinfunction "14_14") (pintype "passive"))
      (node (ref "R53") (pin "2") (pinfunction "2_2") (pintype "passive"))
    )
    (net (code "24") (name "/GPIO5_SEL_15_16") (class "Default")
      (node (ref "JP14") (pin "16") (pinfunction "16_16") (pintype "passive"))
      (node (ref "R54") (pin "2") (pinfunction "2_2") (pintype "passive"))
    )
    (net (code "25") (name "/HWCTRL_JUMPER") (class "Default")
      (node (ref "JP4") (pin "2") (pinfunction "2_2") (pintype "passive"))
      (node (ref "R4") (pin "1") (pinfunction "1_1") (pintype "passive"))
    )
    (net (code "26") (name "/HW_SW_CTRL") (class "Default")
      (node (ref "IC1") (pin "9") (pinfunction "HW_SW_CTRL_9") (pintype "input"))
      (node (ref "JP1") (pin "3") (pinfunction "3_3") (pintype "passive"))
      (node (ref "JP6") (pin "8") (pinfunction "8_8") (pintype "passive"))
      (node (ref "R4") (pin "2") (pinfunction "2_2") (pintype "passive"))
      (node (ref "R7") (pin "1") (pinfunction "1_1") (pintype "passive"))
      (node (ref "R9") (pin "2") (pinfunction "2_2") (pintype "passive"))
    )
    (net (code "27") (name "/LDO_PVCORE_EN") (class "Default")
      (node (ref "IC3") (pin "5") (pinfunction "EN_5") (pintype "passive"))
      (node (ref "R32") (pin "2") (pinfunction "2_2") (pintype "passive"))
    )
    (net (code "28") (name "/LDO_PVCORE_FB") (class "Default")
      (node (ref "IC3") (pin "3") (pinfunction "FB/SNS_3") (pintype "input"))
      (node (ref "R28") (pin "1") (pinfunction "1_1") (pintype "passive"))
      (node (ref "R29") (pin "1") (pinfunction "1_1") (pintype "passive"))
    )
    (net (code "29") (name "/LDO_PVCORE_SS") (class "Default")
      (node (ref "C51") (pin "1") (pinfunction "1_1") (pintype "passive"))
      (node (ref "IC3") (pin "6") (pinfunction "NR/SS_6") (pintype "passive"))
    )
    (net (code "30") (name "/LDO_PVDDIO_EN") (class "Default")
      (node (ref "IC2") (pin "5") (pinfunction "EN_5") (pintype "passive"))
      (node (ref "R31") (pin "2") (pinfunction "2_2") (pintype "passive"))
    )
    (net (code "31") (name "/LDO_PVDDIO_FB") (class "Default")
      (node (ref "IC2") (pin "3") (pinfunction "FB/SNS_3") (pintype "input"))
      (node (ref "R26") (pin "1") (pinfunction "1_1") (pintype "passive"))
      (node (ref "R27") (pin "1") (pinfunction "1_1") (pintype "passive"))
    )
    (net (code "32") (name "/LDO_PVDDIO_SS") (class "Default")
      (node (ref "C49") (pin "1") (pinfunction "1_1") (pintype "passive"))
      (node (ref "IC2") (pin "6") (pinfunction "NR/SS_6") (pintype "passive"))
    )
    (net (code "33") (name "/LF1") (class "Default")
      (node (ref "C48") (pin "1") (pinfunction "1_1") (pintype "passive"))
      (node (ref "IC1") (pin "34") (pinfunction "LF_34") (pintype "passive"))
      (node (ref "R30") (pin "1") (pinfunction "1_1") (pintype "passive"))
    )
    (net (code "34") (name "/LF_FRAC_N") (class "Default")
      (node (ref "C54") (pin "1") (pinfunction "1_1") (pintype "passive"))
      (node (ref "JP8") (pin "3") (pinfunction "3_3") (pintype "passive"))
    )
    (net (code "35") (name "/LF_INT_N\\") (class "Default")
      (node (ref "C53") (pin "1") (pinfunction "1_1") (pintype "passive"))
      (node (ref "JP8") (pin "1") (pinfunction "1_1") (pintype "passive"))
    )
    (net (code "36") (name "/LF_NARROW") (class "Default")
      (node (ref "C55") (pin "1") (pinfunction "1_1") (pintype "passive"))
      (node (ref "JP8") (pin "5") (pinfunction "5_5") (pintype "passive"))
    )
    (net (code "37") (name "/LF_R") (class "Default")
      (node (ref "JP8") (pin "2") (pinfunction "2_2") (pintype "passive"))
      (node (ref "JP8") (pin "4") (pinfunction "4_4") (pintype "passive"))
      (node (ref "JP8") (pin "6") (pinfunction "6_6") (pintype "passive"))
      (node (ref "R30") (pin "2") (pinfunction "2_2") (pintype "passive"))
    )
    (net (code "38") (name "/NC_OUT0_N") (class "Default")
      (node (ref "IC1") (pin "15") (pinfunction "OUT0_N_15") (pintype "output"))
    )
    (net (code "39") (name "/NC_OUT1_N") (class "Default")
      (node (ref "IC1") (pin "16") (pinfunction "OUT1_N_16") (pintype "output"))
    )
    (net (code "40") (name "/NC_OUT1_P") (class "Default")
      (node (ref "IC1") (pin "17") (pinfunction "OUT1_P_17") (pintype "output"))
    )
    (net (code "41") (name "/NC_OUT3_N") (class "Default")
      (node (ref "IC1") (pin "22") (pinfunction "OUT3_N_22") (pintype "output"))
    )
    (net (code "42") (name "/NC_OUT3_P") (class "Default")
      (node (ref "IC1") (pin "23") (pinfunction "OUT3_P_23") (pintype "output"))
    )
    (net (code "43") (name "/NC_OUT4_N") (class "Default")
      (node (ref "IC1") (pin "38") (pinfunction "OUT4_N_38") (pintype "output"))
    )
    (net (code "44") (name "/NC_OUT4_P") (class "Default")
      (node (ref "IC1") (pin "39") (pinfunction "OUT4_P_39") (pintype "output"))
    )
    (net (code "45") (name "/NC_OUT5_N") (class "Default")
      (node (ref "IC1") (pin "41") (pinfunction "OUT5_N_41") (pintype "output"))
    )
    (net (code "46") (name "/NC_OUT5_P") (class "Default")
      (node (ref "IC1") (pin "42") (pinfunction "OUT5_P_42") (pintype "output"))
    )
    (net (code "47") (name "/NC_OUT6_N") (class "Default")
      (node (ref "IC1") (pin "44") (pinfunction "OUT6_N_44") (pintype "output"))
    )
    (net (code "48") (name "/NC_OUT6_P") (class "Default")
      (node (ref "IC1") (pin "45") (pinfunction "OUT6_P_45") (pintype "output"))
    )
    (net (code "49") (name "/NC_OUT7_N") (class "Default")
      (node (ref "IC1") (pin "47") (pinfunction "OUT7_N_47") (pintype "output"))
    )
    (net (code "50") (name "/NC_OUT7_P") (class "Default")
      (node (ref "IC1") (pin "48") (pinfunction "OUT7_P_48") (pintype "output"))
    )
    (net (code "51") (name "/NC_PIN") (class "Default")
      (node (ref "IC1") (pin "29") (pinfunction "NC_29") (pintype "passive"))
    )
    (net (code "52") (name "/NC_USB2ANY_CONN_1") (class "Default")
      (node (ref "JP1") (pin "7") (pinfunction "7_7") (pintype "passive"))
    )
    (net (code "53") (name "/NC_USB2ANY_CONN_2") (class "Default")
      (node (ref "JP1") (pin "8") (pinfunction "8_8") (pintype "passive"))
    )
    (net (code "54") (name "/OUT0_P") (class "Default")
      (node (ref "IC1") (pin "14") (pinfunction "OUT0_P_14") (pintype "output"))
      (node (ref "R17") (pin "2") (pinfunction "2_2") (pintype "passive"))
    )
    (net (code "55") (name "/OUT0_R_C_P") (class "Default")
      (node (ref "C13") (pin "2") (pinfunction "2_2") (pintype "passive"))
      (node (ref "R15") (pin "1") (pinfunction "1_1") (pintype "passive"))
      (node (ref "R16") (pin "2") (pinfunction "2_2") (pintype "passive"))
      (node (ref "X1") (pin "1") (pinfunction "1_1") (pintype "passive"))
    )
    (net (code "56") (name "/OUT0_R_P") (class "Default")
      (node (ref "C13") (pin "1") (pinfunction "1_1") (pintype "passive"))
      (node (ref "R17") (pin "1") (pinfunction "1_1") (pintype "passive"))
    )
    (net (code "57") (name "/OUT2_N") (class "Default")
      (node (ref "IC1") (pin "21") (pinfunction "OUT2_N_21") (pintype "output"))
      (node (ref "R21") (pin "2") (pinfunction "2_2") (pintype "passive"))
    )
    (net (code "58") (name "/OUT2_P") (class "Default")
      (node (ref "IC1") (pin "20") (pinfunction "OUT2_P_20") (pintype "output"))
      (node (ref "R20") (pin "2") (pinfunction "2_2") (pintype "passive"))
    )
    (net (code "59") (name "/OUT2_R_C_N") (class "Default")
      (node (ref "C35") (pin "2") (pinfunction "2_2") (pintype "passive"))
      (node (ref "R24") (pin "2") (pinfunction "2_2") (pintype "passive"))
      (node (ref "R25") (pin "1") (pinfunction "1_1") (pintype "passive"))
      (node (ref "X5") (pin "1") (pinfunction "1_1") (pintype "passive"))
    )
    (net (code "60") (name "/OUT2_R_C_P") (class "Default")
      (node (ref "C34") (pin "2") (pinfunction "2_2") (pintype "passive"))
      (node (ref "R22") (pin "2") (pinfunction "2_2") (pintype "passive"))
      (node (ref "R23") (pin "1") (pinfunction "1_1") (pintype "passive"))
      (node (ref "X3") (pin "1") (pinfunction "1_1") (pintype "passive"))
    )
    (net (code "61") (name "/OUT2_R_N") (class "Default")
      (node (ref "C35") (pin "1") (pinfunction "1_1") (pintype "passive"))
      (node (ref "R21") (pin "1") (pinfunction "1_1") (pintype "passive"))
    )
    (net (code "62") (name "/OUT2_R_P") (class "Default")
      (node (ref "C34") (pin "1") (pinfunction "1_1") (pintype "passive"))
      (node (ref "R20") (pin "1") (pinfunction "1_1") (pintype "passive"))
    )
    (net (code "63") (name "/PDN") (class "Default")
      (node (ref "C4") (pin "1") (pinfunction "1_1") (pintype "passive"))
      (node (ref "IC1") (pin "13") (pinfunction "PDN_13") (pintype "input"))
      (node (ref "JP1") (pin "2") (pinfunction "2_2") (pintype "passive"))
    )
    (net (code "64") (name "/PP_P1V8_VDDO") (class "Default")
      (node (ref "C14") (pin "1") (pinfunction "1_1") (pintype "passive"))
      (node (ref "C15") (pin "1") (pinfunction "1_1") (pintype "passive"))
      (node (ref "C19") (pin "1") (pinfunction "1_1") (pintype "passive"))
      (node (ref "C22") (pin "1") (pinfunction "1_1") (pintype "passive"))
      (node (ref "C25") (pin "1") (pinfunction "1_1") (pintype "passive"))
      (node (ref "C29") (pin "1") (pinfunction "1_1") (pintype "passive"))
      (node (ref "C32") (pin "1") (pinfunction "1_1") (pintype "passive"))
      (node (ref "C33") (pin "1") (pinfunction "1_1") (pintype "passive"))
      (node (ref "C39") (pin "1") (pinfunction "1_1") (pintype "passive"))
      (node (ref "C40") (pin "1") (pinfunction "1_1") (pintype "passive"))
      (node (ref "C45") (pin "1") (pinfunction "1_1") (pintype "passive"))
      (node (ref "IC2") (pin "1") (pinfunction "OUT_2_1") (pintype "output"))
      (node (ref "IC2") (pin "2") (pinfunction "OUT_2") (pintype "output"))
      (node (ref "L3") (pin "2") (pinfunction "P$2_2") (pintype "bidirectional"))
      (node (ref "L4") (pin "2") (pinfunction "P$2_2") (pintype "bidirectional"))
      (node (ref "L5") (pin "2") (pinfunction "P$2_2") (pintype "bidirectional"))
      (node (ref "L6") (pin "2") (pinfunction "P$2_2") (pintype "bidirectional"))
      (node (ref "L7") (pin "2") (pinfunction "P$2_2") (pintype "bidirectional"))
      (node (ref "L8") (pin "2") (pinfunction "P$2_2") (pintype "bidirectional"))
      (node (ref "R15") (pin "2") (pinfunction "2_2") (pintype "passive"))
      (node (ref "R23") (pin "2") (pinfunction "2_2") (pintype "passive"))
      (node (ref "R25") (pin "2") (pinfunction "2_2") (pintype "passive"))
      (node (ref "R27") (pin "2") (pinfunction "2_2") (pintype "passive"))
    )
    (net (code "65") (name "/PP_P3V3_PLL_CORE") (class "Default")
      (node (ref "C2") (pin "1") (pinfunction "1_1") (pintype "passive"))
      (node (ref "C41") (pin "1") (pinfunction "1_1") (pintype "passive"))
      (node (ref "C42") (pin "1") (pinfunction "1_1") (pintype "passive"))
      (node (ref "C43") (pin "1") (pinfunction "1_1") (pintype "passive"))
      (node (ref "C47") (pin "1") (pinfunction "1_1") (pintype "passive"))
      (node (ref "C5") (pin "1") (pinfunction "1_1") (pintype "passive"))
      (node (ref "C6") (pin "1") (pinfunction "1_1") (pintype "passive"))
      (node (ref "IC3") (pin "1") (pinfunction "OUT_2_1") (pintype "output"))
      (node (ref "IC3") (pin "2") (pinfunction "OUT_2") (pintype "output"))
      (node (ref "JP10") (pin "3") (pinfunction "3_3") (pintype "passive"))
      (node (ref "JP11") (pin "3") (pinfunction "3_3") (pintype "passive"))
      (node (ref "JP12") (pin "3") (pinfunction "3_3") (pintype "passive"))
      (node (ref "JP2") (pin "2") (pinfunction "2_2") (pintype "passive"))
      (node (ref "JP3") (pin "3") (pinfunction "3_3") (pintype "passive"))
      (node (ref "JP4") (pin "3") (pinfunction "3_3") (pintype "passive"))
      (node (ref "JP5") (pin "3") (pinfunction "3_3") (pintype "passive"))
      (node (ref "JP9") (pin "3") (pinfunction "3_3") (pintype "passive"))
      (node (ref "L1") (pin "1") (pinfunction "P$1_1") (pintype "bidirectional"))
      (node (ref "L10") (pin "1") (pinfunction "P$1_1") (pintype "bidirectional"))
      (node (ref "L2") (pin "1") (pinfunction "P$1_1") (pintype "bidirectional"))
      (node (ref "L9") (pin "1") (pinfunction "P$1_1") (pintype "bidirectional"))
      (node (ref "R12") (pin "2") (pinfunction "2_2") (pintype "passive"))
      (node (ref "R13") (pin "2") (pinfunction "2_2") (pintype "passive"))
      (node (ref "R18") (pin "2") (pinfunction "2_2") (pintype "passive"))
      (node (ref "R29") (pin "2") (pinfunction "2_2") (pintype "passive"))
      (node (ref "R3") (pin "2") (pinfunction "2_2") (pintype "passive"))
      (node (ref "R31") (pin "1") (pinfunction "1_1") (pintype "passive"))
      (node (ref "R41") (pin "2") (pinfunction "2_2") (pintype "passive"))
      (node (ref "R43") (pin "2") (pinfunction "2_2") (pintype "passive"))
      (node (ref "R44") (pin "2") (pinfunction "2_2") (pintype "passive"))
      (node (ref "R45") (pin "2") (pinfunction "2_2") (pintype "passive"))
      (node (ref "R46") (pin "2") (pinfunction "2_2") (pintype "passive"))
      (node (ref "R7") (pin "2") (pinfunction "2_2") (pintype "passive"))
      (node (ref "R8") (pin "2") (pinfunction "2_2") (pintype "passive"))
    )
    (net (code "66") (name "/PRIREF_N") (class "Default")
      (node (ref "C7") (pin "2") (pinfunction "2_2") (pintype "passive"))
      (node (ref "IC1") (pin "7") (pinfunction "PRIREF_N_7") (pintype "input"))
      (node (ref "R11") (pin "2") (pinfunction "2_2") (pintype "passive"))
    )
    (net (code "67") (name "/PRIREF_P") (class "Default")
      (node (ref "C46") (pin "2") (pinfunction "2_2") (pintype "passive"))
      (node (ref "IC1") (pin "6") (pinfunction "PRIREF_P_6") (pintype "input"))
      (node (ref "R14") (pin "2") (pinfunction "2_2") (pintype "passive"))
    )
    (net (code "68") (name "/PRIREF_R_N") (class "Default")
      (node (ref "C7") (pin "1") (pinfunction "1_1") (pintype "passive"))
      (node (ref "X2") (pin "1") (pinfunction "1_1") (pintype "passive"))
    )
    (net (code "69") (name "/PRIREF_R_P") (class "Default")
      (node (ref "C46") (pin "1") (pinfunction "1_1") (pintype "passive"))
      (node (ref "X4") (pin "1") (pinfunction "1_1") (pintype "passive"))
    )
    (net (code "70") (name "/PRIREF_VCM") (class "Default")
      (node (ref "C1") (pin "1") (pinfunction "1_1") (pintype "passive"))
      (node (ref "JP7") (pin "2") (pinfunction "2_2") (pintype "passive"))
      (node (ref "R11") (pin "1") (pinfunction "1_1") (pintype "passive"))
      (node (ref "R14") (pin "1") (pinfunction "1_1") (pintype "passive"))
    )
    (net (code "71") (name "/PRIREF_VCM_DIVIDER") (class "Default")
      (node (ref "JP7") (pin "3") (pinfunction "3_3") (pintype "passive"))
      (node (ref "R18") (pin "1") (pinfunction "1_1") (pintype "passive"))
      (node (ref "R19") (pin "2") (pinfunction "2_2") (pintype "passive"))
    )
    (net (code "72") (name "/PULLUP_GPIO5") (class "Default")
      (node (ref "JP13") (pin "3") (pinfunction "3_3") (pintype "passive"))
      (node (ref "R41") (pin "1") (pinfunction "1_1") (pintype "passive"))
    )
    (net (code "73") (name "/REFSEL") (class "Default")
      (node (ref "IC1") (pin "8") (pinfunction "REFSEL_8") (pintype "input"))
      (node (ref "JP1") (pin "4") (pinfunction "4_4") (pintype "passive"))
      (node (ref "R10") (pin "2") (pinfunction "2_2") (pintype "passive"))
      (node (ref "R5") (pin "2") (pinfunction "2_2") (pintype "passive"))
      (node (ref "R8") (pin "1") (pinfunction "1_1") (pintype "passive"))
    )
    (net (code "74") (name "/REFSEL_JUMPER") (class "Default")
      (node (ref "JP5") (pin "2") (pinfunction "2_2") (pintype "passive"))
      (node (ref "R5") (pin "1") (pinfunction "1_1") (pintype "passive"))
    )
    (net (code "75") (name "/SCL") (class "Default")
      (node (ref "IC1") (pin "26") (pinfunction "SCL_26") (pintype "bidirectional"))
      (node (ref "JP1") (pin "9") (pinfunction "9_9") (pintype "passive"))
      (node (ref "JP6") (pin "10") (pinfunction "10_10") (pintype "passive"))
      (node (ref "R13") (pin "1") (pinfunction "1_1") (pintype "passive"))
    )
    (net (code "76") (name "/SDA") (class "Default")
      (node (ref "IC1") (pin "25") (pinfunction "SDA_25") (pintype "bidirectional"))
      (node (ref "JP1") (pin "10") (pinfunction "10_10") (pintype "passive"))
      (node (ref "JP6") (pin "9") (pinfunction "9_9") (pintype "passive"))
      (node (ref "R12") (pin "1") (pinfunction "1_1") (pintype "passive"))
    )
    (net (code "77") (name "/SECREF_N") (class "Default")
      (node (ref "C10") (pin "1") (pinfunction "1_1") (pintype "passive"))
      (node (ref "IC1") (pin "11") (pinfunction "SECREF_N_11") (pintype "input"))
      (node (ref "Q1") (pin "1") (pinfunction "1_1") (pintype "passive"))
    )
    (net (code "78") (name "/SECREF_P") (class "Default")
      (node (ref "C3") (pin "1") (pinfunction "1_1") (pintype "passive"))
      (node (ref "IC1") (pin "10") (pinfunction "SECREF_P_10") (pintype "input"))
      (node (ref "Q1") (pin "3") (pinfunction "2_3") (pintype "passive"))
    )
    (net (code "79") (name "/STATUS0") (class "Default")
      (node (ref "IC1") (pin "1") (pinfunction "STATUS0_1") (pintype "output"))
      (node (ref "JP6") (pin "7") (pinfunction "7_7") (pintype "passive"))
      (node (ref "LED2") (pin "C") (pinfunction "C_C") (pintype "passive"))
    )
    (net (code "80") (name "/STATUS1") (class "Default")
      (node (ref "IC1") (pin "2") (pinfunction "STATUS1_2") (pintype "output"))
      (node (ref "JP6") (pin "5") (pinfunction "5_5") (pintype "passive"))
      (node (ref "LED1") (pin "C") (pinfunction "C_C") (pintype "passive"))
    )
    (net (code "81") (name "/STATUS_LED_PWR") (class "Default")
      (node (ref "JP2") (pin "1") (pinfunction "1_1") (pintype "passive"))
      (node (ref "R1") (pin "2") (pinfunction "2_2") (pintype "passive"))
      (node (ref "R2") (pin "2") (pinfunction "2_2") (pintype "passive"))
    )
    (net (code "82") (name "/VDDO_01") (class "Default")
      (node (ref "C104") (pin "1") (pinfunction "1_1") (pintype "passive"))
      (node (ref "C16") (pin "1") (pinfunction "1_1") (pintype "passive"))
      (node (ref "C20") (pin "1") (pinfunction "1_1") (pintype "passive"))
      (node (ref "IC1") (pin "18") (pinfunction "VDDO_01_18") (pintype "power_in"))
      (node (ref "L4") (pin "1") (pinfunction "P$1_1") (pintype "bidirectional"))
    )
    (net (code "83") (name "/VDDO_4") (class "Default")
      (node (ref "C108") (pin "1") (pinfunction "1_1") (pintype "passive"))
      (node (ref "C30") (pin "1") (pinfunction "1_1") (pintype "passive"))
      (node (ref "C31") (pin "1") (pinfunction "1_1") (pintype "passive"))
      (node (ref "IC1") (pin "37") (pinfunction "VDDO_4_37") (pintype "power_in"))
      (node (ref "L8") (pin "1") (pinfunction "P$1_1") (pintype "bidirectional"))
    )
    (net (code "84") (name "/VDDO_5") (class "Default")
      (node (ref "C107") (pin "1") (pinfunction "1_1") (pintype "passive"))
      (node (ref "C26") (pin "1") (pinfunction "1_1") (pintype "passive"))
      (node (ref "C28") (pin "1") (pinfunction "1_1") (pintype "passive"))
      (node (ref "IC1") (pin "40") (pinfunction "VDDO_5_40") (pintype "power_in"))
      (node (ref "L7") (pin "1") (pinfunction "P$1_1") (pintype "bidirectional"))
    )
    (net (code "85") (name "/VDDO_6") (class "Default")
      (node (ref "C105") (pin "1") (pinfunction "1_1") (pintype "passive"))
      (node (ref "C21") (pin "1") (pinfunction "1_1") (pintype "passive"))
      (node (ref "C23") (pin "1") (pinfunction "1_1") (pintype "passive"))
      (node (ref "IC1") (pin "43") (pinfunction "VDDO_6_43") (pintype "power_in"))
      (node (ref "L5") (pin "1") (pinfunction "P$1_1") (pintype "bidirectional"))
    )
    (net (code "86") (name "/VDDO_7") (class "Default")
      (node (ref "C103") (pin "1") (pinfunction "1_1") (pintype "passive"))
      (node (ref "C17") (pin "1") (pinfunction "1_1") (pintype "passive"))
      (node (ref "C18") (pin "1") (pinfunction "1_1") (pintype "passive"))
      (node (ref "IC1") (pin "46") (pinfunction "VDDO_7_46") (pintype "power_in"))
      (node (ref "L3") (pin "1") (pinfunction "P$1_1") (pintype "bidirectional"))
    )
    (net (code "87") (name "/VDDO_23") (class "Default")
      (node (ref "C106") (pin "1") (pinfunction "1_1") (pintype "passive"))
      (node (ref "C24") (pin "1") (pinfunction "1_1") (pintype "passive"))
      (node (ref "C27") (pin "1") (pinfunction "1_1") (pintype "passive"))
      (node (ref "IC1") (pin "19") (pinfunction "VDDO_23_19") (pintype "power_in"))
      (node (ref "L6") (pin "1") (pinfunction "P$1_1") (pintype "bidirectional"))
    )
    (net (code "88") (name "/VDD_DIG") (class "Default")
      (node (ref "C101") (pin "1") (pinfunction "1_1") (pintype "passive"))
      (node (ref "C12") (pin "1") (pinfunction "1_1") (pintype "passive"))
      (node (ref "C9") (pin "1") (pinfunction "1_1") (pintype "passive"))
      (node (ref "IC1") (pin "4") (pinfunction "VDD_DIG_4") (pintype "power_in"))
      (node (ref "L2") (pin "2") (pinfunction "P$2_2") (pintype "bidirectional"))
    )
    (net (code "89") (name "/VDD_IN") (class "Default")
      (node (ref "C100") (pin "1") (pinfunction "1_1") (pintype "passive"))
      (node (ref "C11") (pin "1") (pinfunction "1_1") (pintype "passive"))
      (node (ref "C8") (pin "1") (pinfunction "1_1") (pintype "passive"))
      (node (ref "IC1") (pin "5") (pinfunction "VDD_IN_5") (pintype "power_in"))
      (node (ref "L1") (pin "2") (pinfunction "P$2_2") (pintype "bidirectional"))
    )
    (net (code "90") (name "/VDD_LDO") (class "Default")
      (node (ref "C109") (pin "1") (pinfunction "1_1") (pintype "passive"))
      (node (ref "C36") (pin "1") (pinfunction "1_1") (pintype "passive"))
      (node (ref "C44") (pin "1") (pinfunction "1_1") (pintype "passive"))
      (node (ref "IC1") (pin "27") (pinfunction "VDD_LDO_27") (pintype "power_in"))
      (node (ref "L10") (pin "2") (pinfunction "P$2_2") (pintype "bidirectional"))
    )
    (net (code "91") (name "/VDD_PLL") (class "Default")
      (node (ref "C112") (pin "1") (pinfunction "1_1") (pintype "passive"))
      (node (ref "C37") (pin "1") (pinfunction "1_1") (pintype "passive"))
      (node (ref "C38") (pin "1") (pinfunction "1_1") (pintype "passive"))
      (node (ref "IC1") (pin "36") (pinfunction "VDD_PLL_36") (pintype "power_in"))
      (node (ref "L9") (pin "2") (pinfunction "P$2_2") (pintype "bidirectional"))
    )
    (net (code "92") (name "/VIN_EXT") (class "Default")
      (node (ref "D2") (pin "A") (pinfunction "A_A") (pintype "passive"))
      (node (ref "X6") (pin "2") (pinfunction "S_2") (pintype "passive"))
    )
    (net (code "93") (name "/VIN_MLB") (class "Default")
      (node (ref "D1") (pin "A") (pinfunction "A_A") (pintype "passive"))
      (node (ref "JP6") (pin "1") (pinfunction "1_1") (pintype "passive"))
      (node (ref "JP6") (pin "2") (pinfunction "2_2") (pintype "passive"))
    )
    (net (code "94") (name "GND") (class "Default")
      (node (ref "C1") (pin "2") (pinfunction "2_2") (pintype "passive"))
      (node (ref "C10") (pin "2") (pinfunction "2_2") (pintype "passive"))
      (node (ref "C100") (pin "2") (pinfunction "2_2") (pintype "passive"))
      (node (ref "C101") (pin "2") (pinfunction "2_2") (pintype "passive"))
      (node (ref "C102") (pin "2") (pinfunction "2_2") (pintype "passive"))
      (node (ref "C103") (pin "2") (pinfunction "2_2") (pintype "passive"))
      (node (ref "C104") (pin "2") (pinfunction "2_2") (pintype "passive"))
      (node (ref "C105") (pin "2") (pinfunction "2_2") (pintype "passive"))
      (node (ref "C106") (pin "2") (pinfunction "2_2") (pintype "passive"))
      (node (ref "C107") (pin "2") (pinfunction "2_2") (pintype "passive"))
      (node (ref "C108") (pin "2") (pinfunction "2_2") (pintype "passive"))
      (node (ref "C109") (pin "2") (pinfunction "2_2") (pintype "passive"))
      (node (ref "C11") (pin "2") (pinfunction "2_2") (pintype "passive"))
      (node (ref "C110") (pin "2") (pinfunction "2_2") (pintype "passive"))
      (node (ref "C111") (pin "2") (pinfunction "2_2") (pintype "passive"))
      (node (ref "C112") (pin "2") (pinfunction "2_2") (pintype "passive"))
      (node (ref "C12") (pin "2") (pinfunction "2_2") (pintype "passive"))
      (node (ref "C14") (pin "2") (pinfunction "2_2") (pintype "passive"))
      (node (ref "C15") (pin "2") (pinfunction "2_2") (pintype "passive"))
      (node (ref "C16") (pin "2") (pinfunction "2_2") (pintype "passive"))
      (node (ref "C17") (pin "2") (pinfunction "2_2") (pintype "passive"))
      (node (ref "C18") (pin "2") (pinfunction "2_2") (pintype "passive"))
      (node (ref "C19") (pin "2") (pinfunction "2_2") (pintype "passive"))
      (node (ref "C2") (pin "2") (pinfunction "2_2") (pintype "passive"))
      (node (ref "C20") (pin "2") (pinfunction "2_2") (pintype "passive"))
      (node (ref "C21") (pin "2") (pinfunction "2_2") (pintype "passive"))
      (node (ref "C22") (pin "2") (pinfunction "2_2") (pintype "passive"))
      (node (ref "C23") (pin "2") (pinfunction "2_2") (pintype "passive"))
      (node (ref "C24") (pin "2") (pinfunction "2_2") (pintype "passive"))
      (node (ref "C25") (pin "2") (pinfunction "2_2") (pintype "passive"))
      (node (ref "C26") (pin "2") (pinfunction "2_2") (pintype "passive"))
      (node (ref "C27") (pin "2") (pinfunction "2_2") (pintype "passive"))
      (node (ref "C28") (pin "2") (pinfunction "2_2") (pintype "passive"))
      (node (ref "C29") (pin "2") (pinfunction "2_2") (pintype "passive"))
      (node (ref "C3") (pin "2") (pinfunction "2_2") (pintype "passive"))
      (node (ref "C30") (pin "2") (pinfunction "2_2") (pintype "passive"))
      (node (ref "C31") (pin "2") (pinfunction "2_2") (pintype "passive"))
      (node (ref "C32") (pin "2") (pinfunction "2_2") (pintype "passive"))
      (node (ref "C33") (pin "2") (pinfunction "2_2") (pintype "passive"))
      (node (ref "C36") (pin "2") (pinfunction "2_2") (pintype "passive"))
      (node (ref "C37") (pin "2") (pinfunction "2_2") (pintype "passive"))
      (node (ref "C38") (pin "2") (pinfunction "2_2") (pintype "passive"))
      (node (ref "C39") (pin "2") (pinfunction "2_2") (pintype "passive"))
      (node (ref "C4") (pin "2") (pinfunction "2_2") (pintype "passive"))
      (node (ref "C40") (pin "2") (pinfunction "2_2") (pintype "passive"))
      (node (ref "C41") (pin "2") (pinfunction "2_2") (pintype "passive"))
      (node (ref "C42") (pin "2") (pinfunction "2_2") (pintype "passive"))
      (node (ref "C43") (pin "2") (pinfunction "2_2") (pintype "passive"))
      (node (ref "C44") (pin "2") (pinfunction "2_2") (pintype "passive"))
      (node (ref "C45") (pin "2") (pinfunction "2_2") (pintype "passive"))
      (node (ref "C47") (pin "2") (pinfunction "2_2") (pintype "passive"))
      (node (ref "C48") (pin "2") (pinfunction "2_2") (pintype "passive"))
      (node (ref "C49") (pin "2") (pinfunction "2_2") (pintype "passive"))
      (node (ref "C5") (pin "2") (pinfunction "2_2") (pintype "passive"))
      (node (ref "C50") (pin "2") (pinfunction "2_2") (pintype "passive"))
      (node (ref "C51") (pin "2") (pinfunction "2_2") (pintype "passive"))
      (node (ref "C52") (pin "2") (pinfunction "2_2") (pintype "passive"))
      (node (ref "C53") (pin "2") (pinfunction "2_2") (pintype "passive"))
      (node (ref "C54") (pin "2") (pinfunction "2_2") (pintype "passive"))
      (node (ref "C55") (pin "2") (pinfunction "2_2") (pintype "passive"))
      (node (ref "C56") (pin "2") (pinfunction "2_2") (pintype "passive"))
      (node (ref "C57") (pin "2") (pinfunction "2_2") (pintype "passive"))
      (node (ref "C6") (pin "2") (pinfunction "2_2") (pintype "passive"))
      (node (ref "C8") (pin "2") (pinfunction "2_2") (pintype "passive"))
      (node (ref "C9") (pin "2") (pinfunction "2_2") (pintype "passive"))
      (node (ref "H1") (pin "B3,2") (pinfunction "MOUNT_B3,2") (pintype "passive"))
      (node (ref "H2") (pin "B3,2") (pinfunction "MOUNT_B3,2") (pintype "passive"))
      (node (ref "H3") (pin "B3,2") (pinfunction "MOUNT_B3,2") (pintype "passive"))
      (node (ref "H4") (pin "B3,2") (pinfunction "MOUNT_B3,2") (pintype "passive"))
      (node (ref "IC1") (pin "49") (pinfunction "PAD_49") (pintype "power_in"))
      (node (ref "IC2") (pin "4") (pinfunction "GND_4") (pintype "power_in"))
      (node (ref "IC2") (pin "PAD") (pinfunction "GND_PAD") (pintype "power_in"))
      (node (ref "IC2") (pin "PAD1") (pinfunction "GND_PAD1") (pintype "power_in"))
      (node (ref "IC2") (pin "PAD2") (pinfunction "GND_PAD2") (pintype "power_in"))
      (node (ref "IC2") (pin "PAD3") (pinfunction "GND_PAD3") (pintype "power_in"))
      (node (ref "IC2") (pin "PAD4") (pinfunction "GND_PAD4") (pintype "power_in"))
      (node (ref "IC2") (pin "VIA1") (pinfunction "GND_VIA1") (pintype "power_in"))
      (node (ref "IC2") (pin "VIA2") (pinfunction "GND_VIA2") (pintype "power_in"))
      (node (ref "IC3") (pin "4") (pinfunction "GND_4") (pintype "power_in"))
      (node (ref "IC3") (pin "PAD") (pinfunction "GND_PAD") (pintype "power_in"))
      (node (ref "IC3") (pin "PAD1") (pinfunction "GND_PAD1") (pintype "power_in"))
      (node (ref "IC3") (pin "PAD2") (pinfunction "GND_PAD2") (pintype "power_in"))
      (node (ref "IC3") (pin "PAD3") (pinfunction "GND_PAD3") (pintype "power_in"))
      (node (ref "IC3") (pin "PAD4") (pinfunction "GND_PAD4") (pintype "power_in"))
      (node (ref "IC3") (pin "VIA1") (pinfunction "GND_VIA1") (pintype "power_in"))
      (node (ref "IC3") (pin "VIA2") (pinfunction "GND_VIA2") (pintype "power_in"))
      (node (ref "JP1") (pin "6") (pinfunction "6_6") (pintype "passive"))
      (node (ref "JP10") (pin "1") (pinfunction "1_1") (pintype "passive"))
      (node (ref "JP11") (pin "1") (pinfunction "1_1") (pintype "passive"))
      (node (ref "JP12") (pin "1") (pinfunction "1_1") (pintype "passive"))
      (node (ref "JP13") (pin "1") (pinfunction "1_1") (pintype "passive"))
      (node (ref "JP14") (pin "1") (pinfunction "1_1") (pintype "passive"))
      (node (ref "JP14") (pin "11") (pinfunction "11_11") (pintype "passive"))
      (node (ref "JP14") (pin "13") (pinfunction "13_13") (pintype "passive"))
      (node (ref "JP14") (pin "15") (pinfunction "15_15") (pintype "passive"))
      (node (ref "JP14") (pin "3") (pinfunction "3_3") (pintype "passive"))
      (node (ref "JP14") (pin "5") (pinfunction "5_5") (pintype "passive"))
      (node (ref "JP14") (pin "7") (pinfunction "7_7") (pintype "passive"))
      (node (ref "JP14") (pin "9") (pinfunction "9_9") (pintype "passive"))
      (node (ref "JP3") (pin "1") (pinfunction "1_1") (pintype "passive"))
      (node (ref "JP4") (pin "1") (pinfunction "1_1") (pintype "passive"))
      (node (ref "JP5") (pin "1") (pinfunction "1_1") (pintype "passive"))
      (node (ref "JP6") (pin "3") (pinfunction "3_3") (pintype "passive"))
      (node (ref "JP6") (pin "4") (pinfunction "4_4") (pintype "passive"))
      (node (ref "JP6") (pin "6") (pinfunction "6_6") (pintype "passive"))
      (node (ref "JP7") (pin "1") (pinfunction "1_1") (pintype "passive"))
      (node (ref "JP9") (pin "1") (pinfunction "1_1") (pintype "passive"))
      (node (ref "Q1") (pin "2") (pinfunction "GND_2") (pintype "passive"))
      (node (ref "Q1") (pin "4") (pinfunction "GND_4") (pintype "passive"))
      (node (ref "R10") (pin "1") (pinfunction "1_1") (pintype "passive"))
      (node (ref "R16") (pin "1") (pinfunction "1_1") (pintype "passive"))
      (node (ref "R19") (pin "1") (pinfunction "1_1") (pintype "passive"))
      (node (ref "R22") (pin "1") (pinfunction "1_1") (pintype "passive"))
      (node (ref "R24") (pin "1") (pinfunction "1_1") (pintype "passive"))
      (node (ref "R26") (pin "2") (pinfunction "2_2") (pintype "passive"))
      (node (ref "R28") (pin "2") (pinfunction "2_2") (pintype "passive"))
      (node (ref "R33") (pin "1") (pinfunction "1_1") (pintype "passive"))
      (node (ref "R34") (pin "1") (pinfunction "1_1") (pintype "passive"))
      (node (ref "R35") (pin "1") (pinfunction "1_1") (pintype "passive"))
      (node (ref "R36") (pin "1") (pinfunction "1_1") (pintype "passive"))
      (node (ref "R9") (pin "1") (pinfunction "1_1") (pintype "passive"))
      (node (ref "X1") (pin "G@1") (pinfunction "2_G@1") (pintype "passive"))
      (node (ref "X1") (pin "G@2") (pinfunction "2_G@2") (pintype "passive"))
      (node (ref "X1") (pin "G@3") (pinfunction "2_G@3") (pintype "passive"))
      (node (ref "X1") (pin "G@4") (pinfunction "2_G@4") (pintype "passive"))
      (node (ref "X2") (pin "G@1") (pinfunction "2_G@1") (pintype "passive"))
      (node (ref "X2") (pin "G@2") (pinfunction "2_G@2") (pintype "passive"))
      (node (ref "X2") (pin "G@3") (pinfunction "2_G@3") (pintype "passive"))
      (node (ref "X2") (pin "G@4") (pinfunction "2_G@4") (pintype "passive"))
      (node (ref "X3") (pin "G@1") (pinfunction "2_G@1") (pintype "passive"))
      (node (ref "X3") (pin "G@2") (pinfunction "2_G@2") (pintype "passive"))
      (node (ref "X3") (pin "G@3") (pinfunction "2_G@3") (pintype "passive"))
      (node (ref "X3") (pin "G@4") (pinfunction "2_G@4") (pintype "passive"))
      (node (ref "X4") (pin "G@1") (pinfunction "2_G@1") (pintype "passive"))
      (node (ref "X4") (pin "G@2") (pinfunction "2_G@2") (pintype "passive"))
      (node (ref "X4") (pin "G@3") (pinfunction "2_G@3") (pintype "passive"))
      (node (ref "X4") (pin "G@4") (pinfunction "2_G@4") (pintype "passive"))
      (node (ref "X5") (pin "G@1") (pinfunction "2_G@1") (pintype "passive"))
      (node (ref "X5") (pin "G@2") (pinfunction "2_G@2") (pintype "passive"))
      (node (ref "X5") (pin "G@3") (pinfunction "2_G@3") (pintype "passive"))
      (node (ref "X5") (pin "G@4") (pinfunction "2_G@4") (pintype "passive"))
      (node (ref "X6") (pin "1") (pinfunction "S_1") (pintype "passive"))
    )
    (net (code "95") (name "Net-(IC2-IN)") (class "Default")
      (node (ref "C50") (pin "1") (pinfunction "1_1") (pintype "passive"))
      (node (ref "C52") (pin "1") (pinfunction "1_1") (pintype "passive"))
      (node (ref "C56") (pin "1") (pinfunction "1_1") (pintype "passive"))
      (node (ref "C57") (pin "1") (pinfunction "1_1") (pintype "passive"))
      (node (ref "D1") (pin "C") (pinfunction "C_C") (pintype "passive"))
      (node (ref "D2") (pin "C") (pinfunction "C_C") (pintype "passive"))
      (node (ref "IC2") (pin "7") (pinfunction "IN_2_7") (pintype "input"))
      (node (ref "IC2") (pin "8") (pinfunction "IN_8") (pintype "input"))
      (node (ref "IC3") (pin "7") (pinfunction "IN_2_7") (pintype "input"))
      (node (ref "IC3") (pin "8") (pinfunction "IN_8") (pintype "input"))
      (node (ref "R32") (pin "1") (pinfunction "1_1") (pintype "passive"))
    )
    (net (code "96") (name "Net-(LED1-PadA)") (class "Default")
      (node (ref "LED1") (pin "A") (pinfunction "A_A") (pintype "passive"))
      (node (ref "R1") (pin "1") (pinfunction "1_1") (pintype "passive"))
    )
    (net (code "97") (name "Net-(LED2-PadA)") (class "Default")
      (node (ref "LED2") (pin "A") (pinfunction "A_A") (pintype "passive"))
      (node (ref "R2") (pin "1") (pinfunction "1_1") (pintype "passive"))
    )
  )
)
